# LMS7002M_Data.net
KiCad netlist of a schematic drawn in Altium Designer
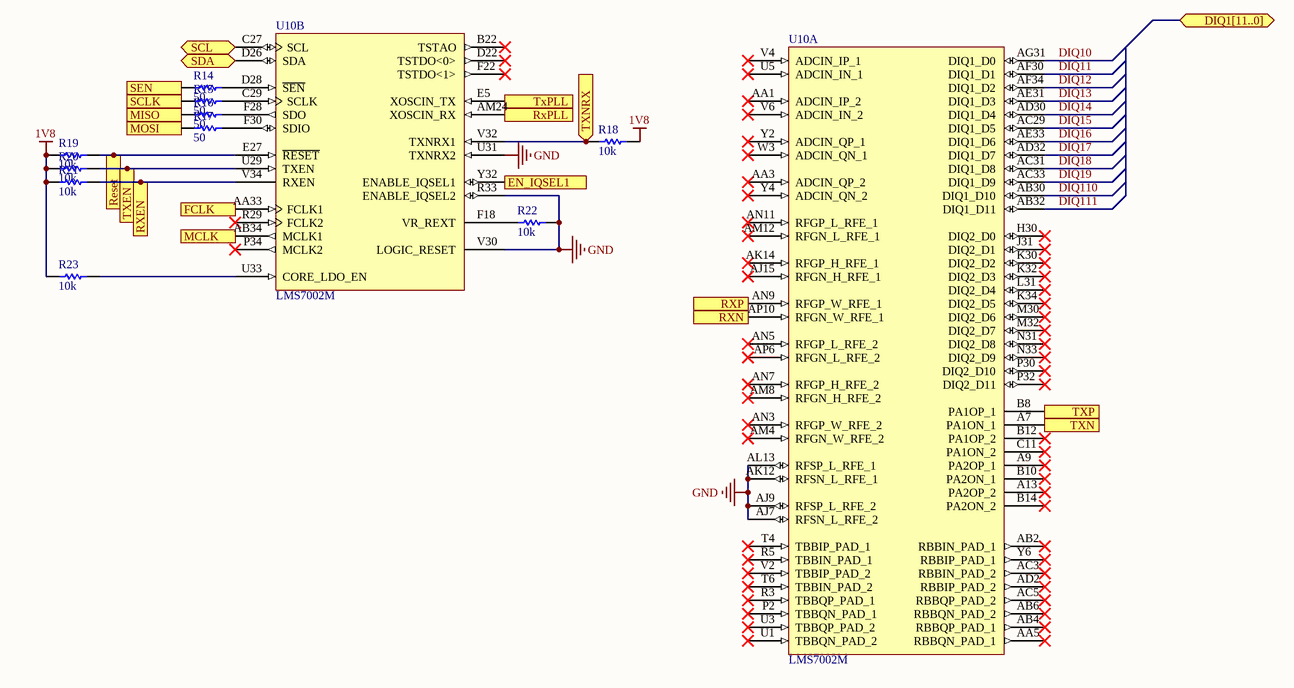
[diagram p0: LMS7002M Data.SchDoc]

(export (version "E")
  (design (tool "Eeschema 10.0.6"))
  (components
    (comp (ref "R14")
      (value "50")
      (footprint "0402-A")
      (description "Resistor")
      (fields (field (name "Comment") "Res1") (field (name "PUBLISHER") "Altium Limited"))
      (libsource (lib "Miscellaneous Devices") (part "Res1"))
    )
    (comp (ref "R15")
      (value "50")
      (footprint "0402-A")
      (description "Resistor")
      (fields (field (name "Comment") "Res1") (field (name "PUBLISHER") "Altium Limited"))
      (libsource (lib "Miscellaneous Devices") (part "Res1"))
    )
    (comp (ref "R16")
      (value "50")
      (footprint "0402-A")
      (description "Resistor")
      (fields (field (name "Comment") "Res1") (field (name "PUBLISHER") "Altium Limited"))
      (libsource (lib "Miscellaneous Devices") (part "Res1"))
    )
    (comp (ref "R17")
      (value "50")
      (footprint "0402-A")
      (description "Resistor")
      (fields (field (name "Comment") "Res1") (field (name "PUBLISHER") "Altium Limited"))
      (libsource (lib "Miscellaneous Devices") (part "Res1"))
    )
    (comp (ref "R18")
      (value "10k")
      (footprint "0402-A")
      (description "Resistor")
      (fields (field (name "Comment") "Res1") (field (name "PUBLISHER") "Altium Limited"))
      (libsource (lib "Miscellaneous Devices") (part "Res1"))
    )
    (comp (ref "R19")
      (value "10k")
      (footprint "0402-A")
      (description "Resistor")
      (fields (field (name "Comment") "Res1") (field (name "PUBLISHER") "Altium Limited"))
      (libsource (lib "Miscellaneous Devices") (part "Res1"))
    )
    (comp (ref "R20")
      (value "10k")
      (footprint "0402-A")
      (description "Resistor")
      (fields (field (name "Comment") "Res1") (field (name "PUBLISHER") "Altium Limited"))
      (libsource (lib "Miscellaneous Devices") (part "Res1"))
    )
    (comp (ref "R21")
      (value "10k")
      (footprint "0402-A")
      (description "Resistor")
      (fields (field (name "Comment") "Res1") (field (name "PUBLISHER") "Altium Limited"))
      (libsource (lib "Miscellaneous Devices") (part "Res1"))
    )
    (comp (ref "R22")
      (value "10k")
      (footprint "0402-A")
      (description "Resistor")
      (fields (field (name "Comment") "Res1") (field (name "PUBLISHER") "Altium Limited"))
      (libsource (lib "Miscellaneous Devices") (part "Res1"))
    )
    (comp (ref "R23")
      (value "10k")
      (footprint "0402-A")
      (description "Resistor")
      (fields (field (name "Comment") "Res1") (field (name "PUBLISHER") "Altium Limited"))
      (libsource (lib "Miscellaneous Devices") (part "Res1"))
    )
    (comp (ref "U10")
      (value "LMS7002M")
      (footprint "LM-QFN-261_V")
      (fields (field (name "MANUFACTURER") "LimeMicrosystemsLtd"))
      (libsource (lib "Altium Content Vault") (part "LM-LMS7002M-QFN-261"))
    )
  )
  (nets
    (net (code "2") (name "/DIQ10") (class "Default")
      (node (ref "U10") (pin "AG31") (pinfunction "DIQ1_D0_AG31") (pintype "bidirectional"))
    )
    (net (code "3") (name "/DIQ11") (class "Default")
      (node (ref "U10") (pin "AF30") (pinfunction "DIQ1_D1_AF30") (pintype "bidirectional"))
    )
    (net (code "4") (name "/DIQ12") (class "Default")
      (node (ref "U10") (pin "AF34") (pinfunction "DIQ1_D2_AF34") (pintype "bidirectional"))
    )
    (net (code "5") (name "/DIQ13") (class "Default")
      (node (ref "U10") (pin "AE31") (pinfunction "DIQ1_D3_AE31") (pintype "bidirectional"))
    )
    (net (code "6") (name "/DIQ14") (class "Default")
      (node (ref "U10") (pin "AD30") (pinfunction "DIQ1_D4_AD30") (pintype "bidirectional"))
    )
    (net (code "7") (name "/DIQ15") (class "Default")
      (node (ref "U10") (pin "AC29") (pinfunction "DIQ1_D5_AC29") (pintype "bidirectional"))
    )
    (net (code "8") (name "/DIQ16") (class "Default")
      (node (ref "U10") (pin "AE33") (pinfunction "DIQ1_D6_AE33") (pintype "bidirectional"))
    )
    (net (code "9") (name "/DIQ17") (class "Default")
      (node (ref "U10") (pin "AD32") (pinfunction "DIQ1_D7_AD32") (pintype "bidirectional"))
    )
    (net (code "10") (name "/DIQ18") (class "Default")
      (node (ref "U10") (pin "AC31") (pinfunction "DIQ1_D8_AC31") (pintype "bidirectional"))
    )
    (net (code "11") (name "/DIQ19") (class "Default")
      (node (ref "U10") (pin "AC33") (pinfunction "DIQ1_D9_AC33") (pintype "bidirectional"))
    )
    (net (code "12") (name "/DIQ110") (class "Default")
      (node (ref "U10") (pin "AB30") (pinfunction "DIQ1_D10_AB30") (pintype "bidirectional"))
    )
    (net (code "13") (name "/DIQ111") (class "Default")
      (node (ref "U10") (pin "AB32") (pinfunction "DIQ1_D11_AB32") (pintype "bidirectional"))
    )
    (net (code "14") (name "/EN_IQSEL1") (class "Default")
      (node (ref "U10") (pin "Y32") (pinfunction "ENABLE_IQSEL1_Y32") (pintype "bidirectional"))
    )
    (net (code "15") (name "/FCLK") (class "Default")
      (node (ref "U10") (pin "AA33") (pinfunction "FCLK1_AA33") (pintype "input"))
    )
    (net (code "16") (name "/MCLK") (class "Default")
      (node (ref "U10") (pin "AB34") (pinfunction "MCLK1_AB34") (pintype "output"))
    )
    (net (code "17") (name "/MISO") (class "Default")
      (node (ref "R16") (pin "2") (pinfunction "2_2") (pintype "passive"))
    )
    (net (code "18") (name "/MOSI") (class "Default")
      (node (ref "R17") (pin "2") (pinfunction "2_2") (pintype "passive"))
    )
    (net (code "19") (name "/RXEN") (class "Default")
      (node (ref "R21") (pin "1") (pinfunction "1_1") (pintype "passive"))
      (node (ref "U10") (pin "V34") (pinfunction "RXEN_V34") (pintype "passive"))
    )
    (net (code "20") (name "/RXN") (class "Default")
      (node (ref "U10") (pin "AP10") (pinfunction "RFGN_W_RFE_1_AP10") (pintype "input"))
    )
    (net (code "21") (name "/RXP") (class "Default")
      (node (ref "U10") (pin "AN9") (pinfunction "RFGP_W_RFE_1_AN9") (pintype "input"))
    )
    (net (code "22") (name "/Reset") (class "Default")
      (node (ref "R19") (pin "1") (pinfunction "1_1") (pintype "passive"))
      (node (ref "U10") (pin "E27") (pinfunction "~{RESET}_E27") (pintype "input"))
    )
    (net (code "23") (name "/RxPLL") (class "Default")
      (node (ref "U10") (pin "AM24") (pinfunction "XOSCIN_RX_AM24") (pintype "input"))
    )
    (net (code "24") (name "/SCL") (class "Default")
      (node (ref "U10") (pin "C27") (pinfunction "SCL_C27") (pintype "bidirectional"))
    )
    (net (code "25") (name "/SCLK") (class "Default")
      (node (ref "R15") (pin "2") (pinfunction "2_2") (pintype "passive"))
    )
    (net (code "26") (name "/SDA") (class "Default")
      (node (ref "U10") (pin "D26") (pinfunction "SDA_D26") (pintype "bidirectional"))
    )
    (net (code "27") (name "/SEN") (class "Default")
      (node (ref "R14") (pin "2") (pinfunction "2_2") (pintype "passive"))
    )
    (net (code "28") (name "/TXEN") (class "Default")
      (node (ref "R20") (pin "1") (pinfunction "1_1") (pintype "passive"))
      (node (ref "U10") (pin "U29") (pinfunction "TXEN_U29") (pintype "input"))
    )
    (net (code "29") (name "/TXN") (class "Default")
      (node (ref "U10") (pin "A7") (pinfunction "PA1ON_1_A7") (pintype "open_collector"))
    )
    (net (code "30") (name "/TXNRX") (class "Default")
      (node (ref "R18") (pin "2") (pinfunction "2_2") (pintype "passive"))
      (node (ref "U10") (pin "V32") (pinfunction "TXNRX1_V32") (pintype "input"))
    )
    (net (code "31") (name "/TXP") (class "Default")
      (node (ref "U10") (pin "B8") (pinfunction "PA1OP_1_B8") (pintype "open_collector"))
    )
    (net (code "32") (name "/TxPLL") (class "Default")
      (node (ref "U10") (pin "E5") (pinfunction "XOSCIN_TX_E5") (pintype "input"))
    )
    (net (code "33") (name "1V8") (class "Default")
      (node (ref "R18") (pin "1") (pinfunction "1_1") (pintype "passive"))
      (node (ref "R19") (pin "2") (pinfunction "2_2") (pintype "passive"))
      (node (ref "R20") (pin "2") (pinfunction "2_2") (pintype "passive"))
      (node (ref "R21") (pin "2") (pinfunction "2_2") (pintype "passive"))
      (node (ref "R23") (pin "2") (pinfunction "2_2") (pintype "passive"))
    )
    (net (code "34") (name "GND") (class "Default")
      (node (ref "R22") (pin "1") (pinfunction "1_1") (pintype "passive"))
      (node (ref "U10") (pin "AJ7") (pinfunction "RFSN_L_RFE_2_AJ7") (pintype "bidirectional"))
      (node (ref "U10") (pin "AJ9") (pinfunction "RFSP_L_RFE_2_AJ9") (pintype "bidirectional"))
      (node (ref "U10") (pin "AK12") (pinfunction "RFSN_L_RFE_1_AK12") (pintype "bidirectional"))
      (node (ref "U10") (pin "AL13") (pinfunction "RFSP_L_RFE_1_AL13") (pintype "bidirectional"))
      (node (ref "U10") (pin "R33") (pinfunction "ENABLE_IQSEL2_R33") (pintype "bidirectional"))
      (node (ref "U10") (pin "U31") (pinfunction "TXNRX2_U31") (pintype "input"))
      (node (ref "U10") (pin "V30") (pinfunction "LOGIC_RESET_V30") (pintype "passive"))
    )
    (net (code "35") (name "Net-(U10B-CORE_LDO_EN)") (class "Default")
      (node (ref "R23") (pin "1") (pinfunction "1_1") (pintype "passive"))
      (node (ref "U10") (pin "U33") (pinfunction "CORE_LDO_EN_U33") (pintype "input"))
    )
    (net (code "36") (name "Net-(U10B-SCLK)") (class "Default")
      (node (ref "R15") (pin "1") (pinfunction "1_1") (pintype "passive"))
      (node (ref "U10") (pin "C29") (pinfunction "SCLK_C29") (pintype "input"))
    )
    (net (code "37") (name "Net-(U10B-SDIO)") (class "Default")
      (node (ref "R17") (pin "1") (pinfunction "1_1") (pintype "passive"))
      (node (ref "U10") (pin "F30") (pinfunction "SDIO_F30") (pintype "bidirectional"))
    )
    (net (code "38") (name "Net-(U10B-SDO)") (class "Default")
      (node (ref "R16") (pin "1") (pinfunction "1_1") (pintype "passive"))
      (node (ref "U10") (pin "F28") (pinfunction "SDO_F28") (pintype "output"))
    )
    (net (code "39") (name "Net-(U10B-VR_REXT)") (class "Default")
      (node (ref "R22") (pin "2") (pinfunction "2_2") (pintype "passive"))
      (node (ref "U10") (pin "F18") (pinfunction "VR_REXT_F18") (pintype "passive"))
    )
    (net (code "40") (name "Net-(U10B-~{SEN})") (class "Default")
      (node (ref "R14") (pin "1") (pinfunction "1_1") (pintype "passive"))
      (node (ref "U10") (pin "D28") (pinfunction "~{SEN}_D28") (pintype "input"))
    )
    (net (code "41") (name "unconnected-(U10A-ADCIN_IN_1-PadU5)") (class "Default")
      (node (ref "U10") (pin "U5") (pinfunction "ADCIN_IN_1_U5") (pintype "input+no_connect"))
    )
    (net (code "42") (name "unconnected-(U10A-ADCIN_IN_2-PadV6)") (class "Default")
      (node (ref "U10") (pin "V6") (pinfunction "ADCIN_IN_2_V6") (pintype "input+no_connect"))
    )
    (net (code "43") (name "unconnected-(U10A-ADCIN_IP_1-PadV4)") (class "Default")
      (node (ref "U10") (pin "V4") (pinfunction "ADCIN_IP_1_V4") (pintype "input+no_connect"))
    )
    (net (code "44") (name "unconnected-(U10A-ADCIN_IP_2-PadAA1)") (class "Default")
      (node (ref "U10") (pin "AA1") (pinfunction "ADCIN_IP_2_AA1") (pintype "input+no_connect"))
    )
    (net (code "45") (name "unconnected-(U10A-ADCIN_QN_1-PadW3)") (class "Default")
      (node (ref "U10") (pin "W3") (pinfunction "ADCIN_QN_1_W3") (pintype "input+no_connect"))
    )
    (net (code "46") (name "unconnected-(U10A-ADCIN_QN_2-PadY4)") (class "Default")
      (node (ref "U10") (pin "Y4") (pinfunction "ADCIN_QN_2_Y4") (pintype "input+no_connect"))
    )
    (net (code "47") (name "unconnected-(U10A-ADCIN_QP_1-PadY2)") (class "Default")
      (node (ref "U10") (pin "Y2") (pinfunction "ADCIN_QP_1_Y2") (pintype "input+no_connect"))
    )
    (net (code "48") (name "unconnected-(U10A-ADCIN_QP_2-PadAA3)") (class "Default")
      (node (ref "U10") (pin "AA3") (pinfunction "ADCIN_QP_2_AA3") (pintype "input+no_connect"))
    )
    (net (code "49") (name "unconnected-(U10A-DIQ2_D0-PadH30)") (class "Default")
      (node (ref "U10") (pin "H30") (pinfunction "DIQ2_D0_H30") (pintype "bidirectional+no_connect"))
    )
    (net (code "50") (name "unconnected-(U10A-DIQ2_D1-PadJ31)") (class "Default")
      (node (ref "U10") (pin "J31") (pinfunction "DIQ2_D1_J31") (pintype "bidirectional+no_connect"))
    )
    (net (code "51") (name "unconnected-(U10A-DIQ2_D2-PadK30)") (class "Default")
      (node (ref "U10") (pin "K30") (pinfunction "DIQ2_D2_K30") (pintype "bidirectional+no_connect"))
    )
    (net (code "52") (name "unconnected-(U10A-DIQ2_D3-PadK32)") (class "Default")
      (node (ref "U10") (pin "K32") (pinfunction "DIQ2_D3_K32") (pintype "bidirectional+no_connect"))
    )
    (net (code "53") (name "unconnected-(U10A-DIQ2_D4-PadL31)") (class "Default")
      (node (ref "U10") (pin "L31") (pinfunction "DIQ2_D4_L31") (pintype "bidirectional+no_connect"))
    )
    (net (code "54") (name "unconnected-(U10A-DIQ2_D5-PadK34)") (class "Default")
      (node (ref "U10") (pin "K34") (pinfunction "DIQ2_D5_K34") (pintype "bidirectional+no_connect"))
    )
    (net (code "55") (name "unconnected-(U10A-DIQ2_D6-PadM30)") (class "Default")
      (node (ref "U10") (pin "M30") (pinfunction "DIQ2_D6_M30") (pintype "bidirectional+no_connect"))
    )
    (net (code "56") (name "unconnected-(U10A-DIQ2_D7-PadM32)") (class "Default")
      (node (ref "U10") (pin "M32") (pinfunction "DIQ2_D7_M32") (pintype "bidirectional+no_connect"))
    )
    (net (code "57") (name "unconnected-(U10A-DIQ2_D8-PadN31)") (class "Default")
      (node (ref "U10") (pin "N31") (pinfunction "DIQ2_D8_N31") (pintype "bidirectional+no_connect"))
    )
    (net (code "58") (name "unconnected-(U10A-DIQ2_D9-PadN33)") (class "Default")
      (node (ref "U10") (pin "N33") (pinfunction "DIQ2_D9_N33") (pintype "bidirectional+no_connect"))
    )
    (net (code "59") (name "unconnected-(U10A-DIQ2_D10-PadP30)") (class "Default")
      (node (ref "U10") (pin "P30") (pinfunction "DIQ2_D10_P30") (pintype "bidirectional+no_connect"))
    )
    (net (code "60") (name "unconnected-(U10A-DIQ2_D11-PadP32)") (class "Default")
      (node (ref "U10") (pin "P32") (pinfunction "DIQ2_D11_P32") (pintype "bidirectional+no_connect"))
    )
    (net (code "61") (name "unconnected-(U10A-PA1ON_2-PadC11)") (class "Default")
      (node (ref "U10") (pin "C11") (pinfunction "PA1ON_2_C11") (pintype "open_collector+no_connect"))
    )
    (net (code "62") (name "unconnected-(U10A-PA1OP_2-PadB12)") (class "Default")
      (node (ref "U10") (pin "B12") (pinfunction "PA1OP_2_B12") (pintype "open_collector+no_connect"))
    )
    (net (code "63") (name "unconnected-(U10A-PA2ON_1-PadB10)") (class "Default")
      (node (ref "U10") (pin "B10") (pinfunction "PA2ON_1_B10") (pintype "open_collector+no_connect"))
    )
    (net (code "64") (name "unconnected-(U10A-PA2ON_2-PadB14)") (class "Default")
      (node (ref "U10") (pin "B14") (pinfunction "PA2ON_2_B14") (pintype "open_collector+no_connect"))
    )
    (net (code "65") (name "unconnected-(U10A-PA2OP_1-PadA9)") (class "Default")
      (node (ref "U10") (pin "A9") (pinfunction "PA2OP_1_A9") (pintype "open_collector+no_connect"))
    )
    (net (code "66") (name "unconnected-(U10A-PA2OP_2-PadA13)") (class "Default")
      (node (ref "U10") (pin "A13") (pinfunction "PA2OP_2_A13") (pintype "open_collector+no_connect"))
    )
    (net (code "67") (name "unconnected-(U10A-RBBIN_PAD_1-PadAB2)") (class "Default")
      (node (ref "U10") (pin "AB2") (pinfunction "RBBIN_PAD_1_AB2") (pintype "output+no_connect"))
    )
    (net (code "68") (name "unconnected-(U10A-RBBIN_PAD_2-PadAC3)") (class "Default")
      (node (ref "U10") (pin "AC3") (pinfunction "RBBIN_PAD_2_AC3") (pintype "output+no_connect"))
    )
    (net (code "69") (name "unconnected-(U10A-RBBIP_PAD_1-PadY6)") (class "Default")
      (node (ref "U10") (pin "Y6") (pinfunction "RBBIP_PAD_1_Y6") (pintype "output+no_connect"))
    )
    (net (code "70") (name "unconnected-(U10A-RBBIP_PAD_2-PadAD2)") (class "Default")
      (node (ref "U10") (pin "AD2") (pinfunction "RBBIP_PAD_2_AD2") (pintype "output+no_connect"))
    )
    (net (code "71") (name "unconnected-(U10A-RBBQN_PAD_1-PadAA5)") (class "Default")
      (node (ref "U10") (pin "AA5") (pinfunction "RBBQN_PAD_1_AA5") (pintype "output+no_connect"))
    )
    (net (code "72") (name "unconnected-(U10A-RBBQN_PAD_2-PadAB6)") (class "Default")
      (node (ref "U10") (pin "AB6") (pinfunction "RBBQN_PAD_2_AB6") (pintype "output+no_connect"))
    )
    (net (code "73") (name "unconnected-(U10A-RBBQP_PAD_1-PadAB4)") (class "Default")
      (node (ref "U10") (pin "AB4") (pinfunction "RBBQP_PAD_1_AB4") (pintype "output+no_connect"))
    )
    (net (code "74") (name "unconnected-(U10A-RBBQP_PAD_2-PadAC5)") (class "Default")
      (node (ref "U10") (pin "AC5") (pinfunction "RBBQP_PAD_2_AC5") (pintype "output+no_connect"))
    )
    (net (code "75") (name "unconnected-(U10A-RFGN_H_RFE_1-PadAJ15)") (class "Default")
      (node (ref "U10") (pin "AJ15") (pinfunction "RFGN_H_RFE_1_AJ15") (pintype "input+no_connect"))
    )
    (net (code "76") (name "unconnected-(U10A-RFGN_H_RFE_2-PadAM8)") (class "Default")
      (node (ref "U10") (pin "AM8") (pinfunction "RFGN_H_RFE_2_AM8") (pintype "input+no_connect"))
    )
    (net (code "77") (name "unconnected-(U10A-RFGN_L_RFE_1-PadAM12)") (class "Default")
      (node (ref "U10") (pin "AM12") (pinfunction "RFGN_L_RFE_1_AM12") (pintype "input+no_connect"))
    )
    (net (code "78") (name "unconnected-(U10A-RFGN_L_RFE_2-PadAP6)") (class "Default")
      (node (ref "U10") (pin "AP6") (pinfunction "RFGN_L_RFE_2_AP6") (pintype "input+no_connect"))
    )
    (net (code "79") (name "unconnected-(U10A-RFGN_W_RFE_2-PadAM4)") (class "Default")
      (node (ref "U10") (pin "AM4") (pinfunction "RFGN_W_RFE_2_AM4") (pintype "input+no_connect"))
    )
    (net (code "80") (name "unconnected-(U10A-RFGP_H_RFE_1-PadAK14)") (class "Default")
      (node (ref "U10") (pin "AK14") (pinfunction "RFGP_H_RFE_1_AK14") (pintype "input+no_connect"))
    )
    (net (code "81") (name "unconnected-(U10A-RFGP_H_RFE_2-PadAN7)") (class "Default")
      (node (ref "U10") (pin "AN7") (pinfunction "RFGP_H_RFE_2_AN7") (pintype "input+no_connect"))
    )
    (net (code "82") (name "unconnected-(U10A-RFGP_L_RFE_1-PadAN11)") (class "Default")
      (node (ref "U10") (pin "AN11") (pinfunction "RFGP_L_RFE_1_AN11") (pintype "input+no_connect"))
    )
    (net (code "83") (name "unconnected-(U10A-RFGP_L_RFE_2-PadAN5)") (class "Default")
      (node (ref "U10") (pin "AN5") (pinfunction "RFGP_L_RFE_2_AN5") (pintype "input+no_connect"))
    )
    (net (code "84") (name "unconnected-(U10A-RFGP_W_RFE_2-PadAN3)") (class "Default")
      (node (ref "U10") (pin "AN3") (pinfunction "RFGP_W_RFE_2_AN3") (pintype "input+no_connect"))
    )
    (net (code "85") (name "unconnected-(U10A-TBBIN_PAD_1-PadR5)") (class "Default")
      (node (ref "U10") (pin "R5") (pinfunction "TBBIN_PAD_1_R5") (pintype "input+no_connect"))
    )
    (net (code "86") (name "unconnected-(U10A-TBBIN_PAD_2-PadT6)") (class "Default")
      (node (ref "U10") (pin "T6") (pinfunction "TBBIN_PAD_2_T6") (pintype "input+no_connect"))
    )
    (net (code "87") (name "unconnected-(U10A-TBBIP_PAD_1-PadT4)") (class "Default")
      (node (ref "U10") (pin "T4") (pinfunction "TBBIP_PAD_1_T4") (pintype "input+no_connect"))
    )
    (net (code "88") (name "unconnected-(U10A-TBBIP_PAD_2-PadV2)") (class "Default")
      (node (ref "U10") (pin "V2") (pinfunction "TBBIP_PAD_2_V2") (pintype "input+no_connect"))
    )
    (net (code "89") (name "unconnected-(U10A-TBBQN_PAD_1-PadP2)") (class "Default")
      (node (ref "U10") (pin "P2") (pinfunction "TBBQN_PAD_1_P2") (pintype "input+no_connect"))
    )
    (net (code "90") (name "unconnected-(U10A-TBBQN_PAD_2-PadU1)") (class "Default")
      (node (ref "U10") (pin "U1") (pinfunction "TBBQN_PAD_2_U1") (pintype "input+no_connect"))
    )
    (net (code "91") (name "unconnected-(U10A-TBBQP_PAD_1-PadR3)") (class "Default")
      (node (ref "U10") (pin "R3") (pinfunction "TBBQP_PAD_1_R3") (pintype "input+no_connect"))
    )
    (net (code "92") (name "unconnected-(U10A-TBBQP_PAD_2-PadU3)") (class "Default")
      (node (ref "U10") (pin "U3") (pinfunction "TBBQP_PAD_2_U3") (pintype "input+no_connect"))
    )
    (net (code "93") (name "unconnected-(U10B-FCLK2-PadR29)") (class "Default")
      (node (ref "U10") (pin "R29") (pinfunction "FCLK2_R29") (pintype "input+no_connect"))
    )
    (net (code "94") (name "unconnected-(U10B-MCLK2-PadP34)") (class "Default")
      (node (ref "U10") (pin "P34") (pinfunction "MCLK2_P34") (pintype "output+no_connect"))
    )
    (net (code "95") (name "unconnected-(U10B-TSTAO-PadB22)") (class "Default")
      (node (ref "U10") (pin "B22") (pinfunction "TSTAO_B22") (pintype "output+no_connect"))
    )
    (net (code "96") (name "unconnected-(U10B-TSTDO<0>-PadD22)") (class "Default")
      (node (ref "U10") (pin "D22") (pinfunction "TSTDO<0>_D22") (pintype "output+no_connect"))
    )
    (net (code "97") (name "unconnected-(U10B-TSTDO<1>-PadF22)") (class "Default")
      (node (ref "U10") (pin "F22") (pinfunction "TSTDO<1>_F22") (pintype "output+no_connect"))
    )
  )
)
